# WiFiRadio.net
KiCad netlist of a schematic drawn in EAGLE
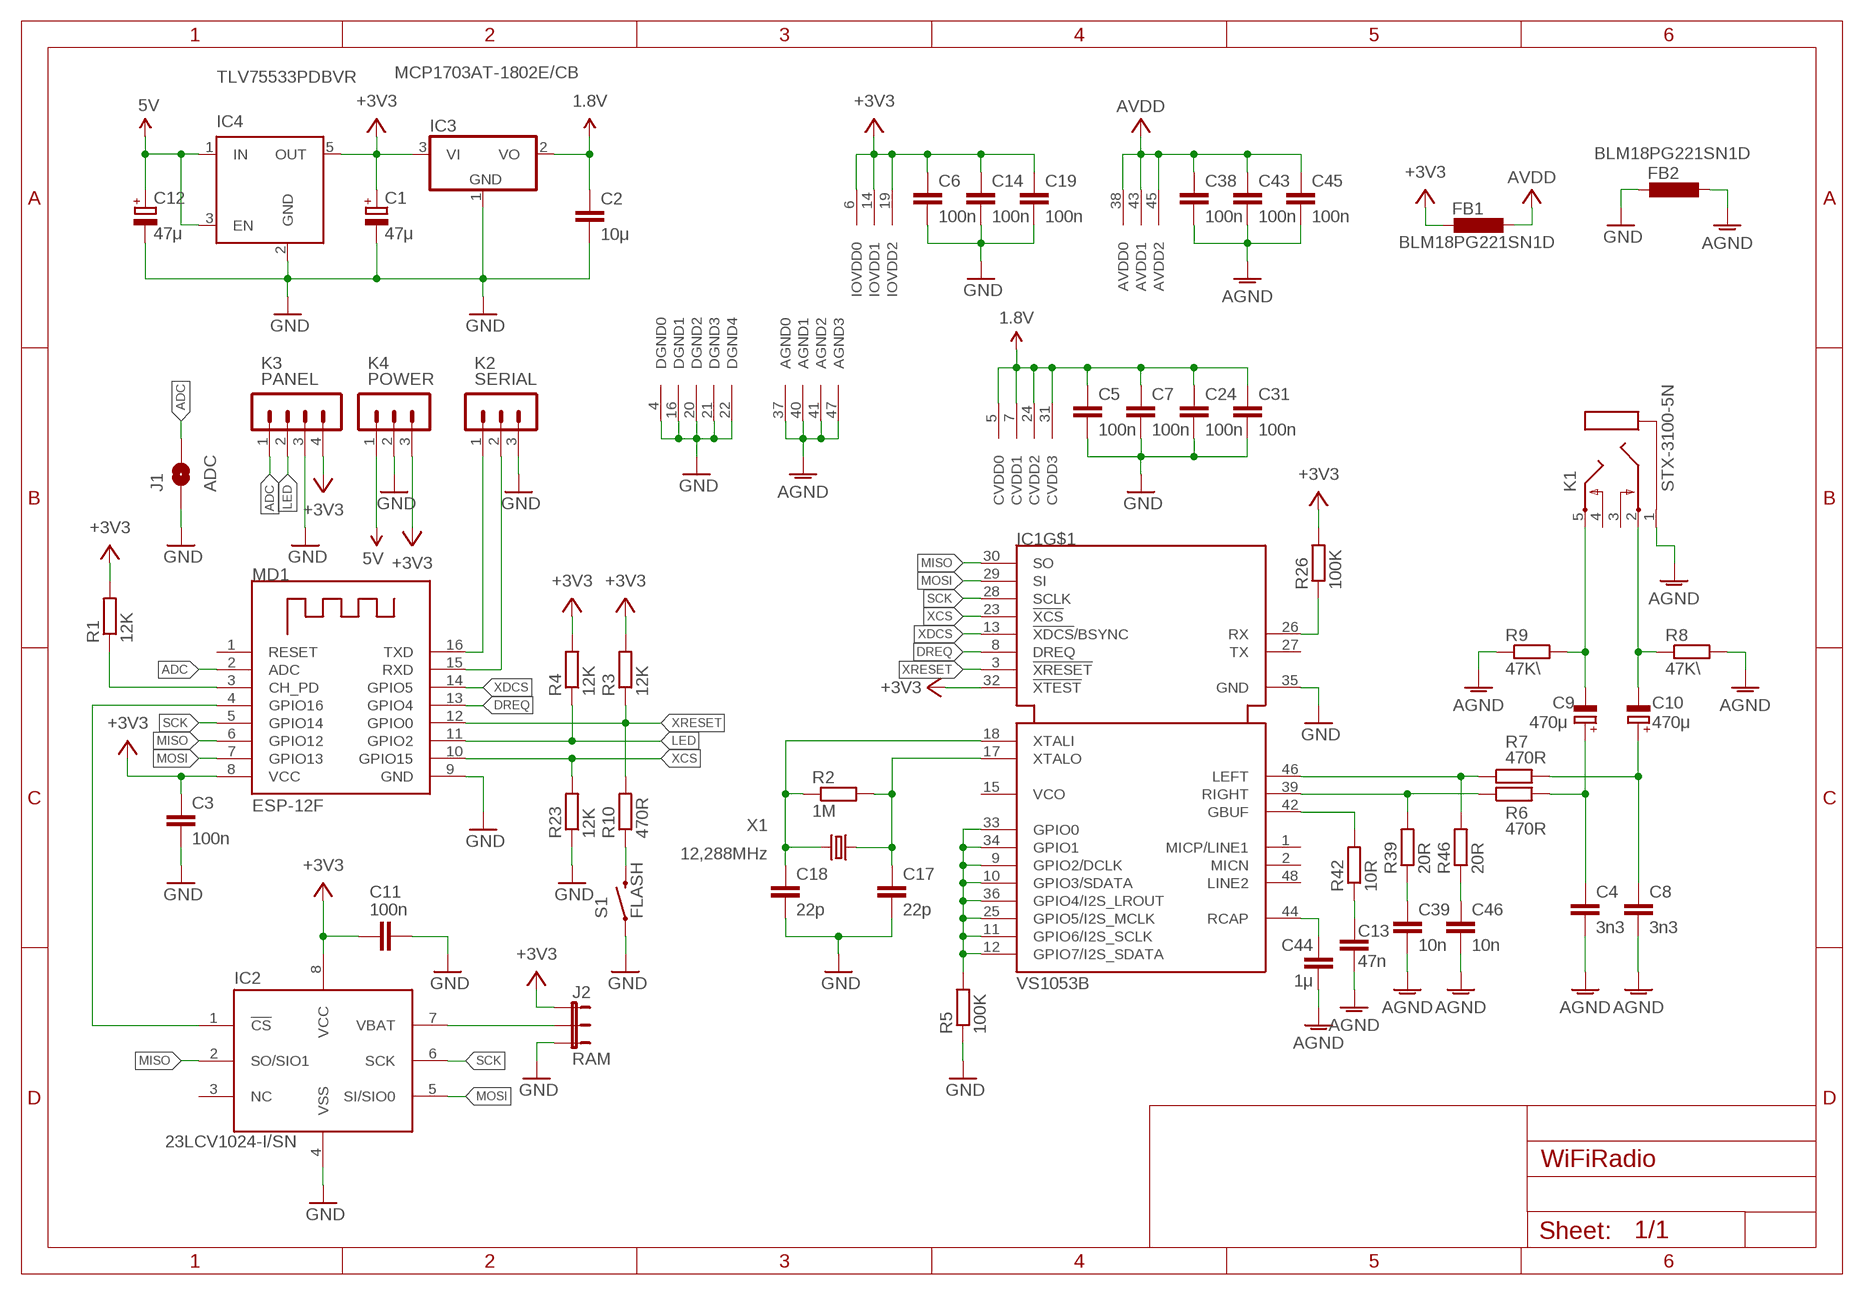
[diagram p0: schematic, sheet 1]

(export (version "E")
  (design (tool "Eeschema 10.0.6"))
  (components
    (comp (ref "C1")
      (value "47μ")
      (footprint "eagle-import:SMC_B")
      (libsource (lib "eagle-import") (part "rcl_334_CPOL-EUSMCB"))
    )
    (comp (ref "C2")
      (value "10μ")
      (footprint "eagle-import:C0805")
      (libsource (lib "eagle-import") (part "C-EUC0805"))
    )
    (comp (ref "C3")
      (value "100n")
      (footprint "eagle-import:C0603")
      (libsource (lib "eagle-import") (part "C-EUC0603"))
    )
    (comp (ref "C4")
      (value "3n3")
      (footprint "eagle-import:C0805")
      (libsource (lib "eagle-import") (part "C-EUC0805"))
    )
    (comp (ref "C5")
      (value "100n")
      (footprint "eagle-import:C0603")
      (libsource (lib "eagle-import") (part "C-EUC0603"))
    )
    (comp (ref "C6")
      (value "100n")
      (footprint "eagle-import:C0603")
      (libsource (lib "eagle-import") (part "C-EUC0603"))
    )
    (comp (ref "C7")
      (value "100n")
      (footprint "eagle-import:C0603")
      (libsource (lib "eagle-import") (part "C-EUC0603"))
    )
    (comp (ref "C8")
      (value "3n3")
      (footprint "eagle-import:C0805")
      (libsource (lib "eagle-import") (part "C-EUC0805"))
    )
    (comp (ref "C9")
      (value "470μ")
      (footprint "eagle-import:E3,5-8")
      (libsource (lib "eagle-import") (part "CPOL-EUE3.5-8"))
    )
    (comp (ref "C10")
      (value "470μ")
      (footprint "eagle-import:E3,5-8")
      (libsource (lib "eagle-import") (part "CPOL-EUE3.5-8"))
    )
    (comp (ref "C11")
      (value "100n")
      (footprint "eagle-import:C0603")
      (libsource (lib "eagle-import") (part "C-EUC0603"))
    )
    (comp (ref "C12")
      (value "47μ")
      (footprint "eagle-import:SMC_B")
      (libsource (lib "eagle-import") (part "rcl_334_CPOL-EUSMCB"))
    )
    (comp (ref "C13")
      (value "47n")
      (footprint "eagle-import:C0805")
      (libsource (lib "eagle-import") (part "C-EUC0805"))
    )
    (comp (ref "C14")
      (value "100n")
      (footprint "eagle-import:C0603")
      (libsource (lib "eagle-import") (part "C-EUC0603"))
    )
    (comp (ref "C17")
      (value "22p")
      (footprint "eagle-import:C0805")
      (libsource (lib "eagle-import") (part "C-EUC0805"))
    )
    (comp (ref "C18")
      (value "22p")
      (footprint "eagle-import:C0805")
      (libsource (lib "eagle-import") (part "C-EUC0805"))
    )
    (comp (ref "C19")
      (value "100n")
      (footprint "eagle-import:C0603")
      (libsource (lib "eagle-import") (part "C-EUC0603"))
    )
    (comp (ref "C24")
      (value "100n")
      (footprint "eagle-import:C0603")
      (libsource (lib "eagle-import") (part "C-EUC0603"))
    )
    (comp (ref "C31")
      (value "100n")
      (footprint "eagle-import:C0603")
      (libsource (lib "eagle-import") (part "C-EUC0603"))
    )
    (comp (ref "C38")
      (value "100n")
      (footprint "eagle-import:C0603")
      (libsource (lib "eagle-import") (part "C-EUC0603"))
    )
    (comp (ref "C39")
      (value "10n")
      (footprint "eagle-import:C0805")
      (libsource (lib "eagle-import") (part "C-EUC0805"))
    )
    (comp (ref "C43")
      (value "100n")
      (footprint "eagle-import:C0603")
      (libsource (lib "eagle-import") (part "C-EUC0603"))
    )
    (comp (ref "C44")
      (value "1μ")
      (footprint "eagle-import:C0805")
      (libsource (lib "eagle-import") (part "C-EUC0805"))
    )
    (comp (ref "C45")
      (value "100n")
      (footprint "eagle-import:C0603")
      (libsource (lib "eagle-import") (part "C-EUC0603"))
    )
    (comp (ref "C46")
      (value "10n")
      (footprint "eagle-import:C0805")
      (libsource (lib "eagle-import") (part "C-EUC0805"))
    )
    (comp (ref "FB1")
      (value "BLM18PG221SN1D")
      (footprint "eagle-import:L2012C")
      (libsource (lib "eagle-import") (part "L-EUL2012C"))
    )
    (comp (ref "FB2")
      (value "BLM18PG221SN1D")
      (footprint "eagle-import:L2012C")
      (libsource (lib "eagle-import") (part "L-EUL2012C"))
    )
    (comp (ref "IC1")
      (value "VS1053B")
      (footprint "eagle-import:LQFP48")
      (libsource (lib "eagle-import") (part "VS1053B"))
    )
    (comp (ref "IC2")
      (value "23LCV1024-I/SN")
      (footprint "eagle-import:SO-08")
      (libsource (lib "eagle-import") (part "23LCV1024-I/SN"))
    )
    (comp (ref "IC3")
      (value "MCP1703AT-1802E/CB")
      (footprint "eagle-import:SOT23")
      (libsource (lib "eagle-import") (part "MCP1703CB"))
    )
    (comp (ref "IC4")
      (value "TLV75533PDBVR")
      (footprint "eagle-import:SOT23-5")
      (libsource (lib "eagle-import") (part "TLV7555P-DBV"))
    )
    (comp (ref "J1")
      (value "ADC")
      (footprint "eagle-import:SJ_2S")
      (libsource (lib "eagle-import") (part "SOLDERJUMPER-OLDNC"))
    )
    (comp (ref "J2")
      (value "RAM")
      (footprint "eagle-import:SJ_3")
      (libsource (lib "eagle-import") (part "JUMPER-3SMD"))
    )
    (comp (ref "K1")
      (value "STX-3100-5N")
      (footprint "eagle-import:STX3100")
      (libsource (lib "eagle-import") (part "STEREOJACK"))
    )
    (comp (ref "K2")
      (value "SERIAL")
      (footprint "eagle-import:MA03-1")
      (libsource (lib "eagle-import") (part "MA03-1"))
    )
    (comp (ref "K3")
      (value "PANEL")
      (footprint "eagle-import:MA04-1")
      (libsource (lib "eagle-import") (part "MA04-1"))
    )
    (comp (ref "K4")
      (value "POWER")
      (footprint "eagle-import:MA03-1")
      (libsource (lib "eagle-import") (part "MA03-1"))
    )
    (comp (ref "MD1")
      (value "ESP-12F")
      (footprint "eagle-import:ESP-12F")
      (libsource (lib "eagle-import") (part "ESP-12F"))
    )
    (comp (ref "R1")
      (value "12K")
      (footprint "eagle-import:R0805")
      (libsource (lib "eagle-import") (part "R-EU_R0805"))
    )
    (comp (ref "R2")
      (value "1M")
      (footprint "eagle-import:R0805")
      (libsource (lib "eagle-import") (part "R-EU_R0805"))
    )
    (comp (ref "R3")
      (value "12K")
      (footprint "eagle-import:R0805")
      (libsource (lib "eagle-import") (part "R-EU_R0805"))
    )
    (comp (ref "R4")
      (value "12K")
      (footprint "eagle-import:R0805")
      (libsource (lib "eagle-import") (part "R-EU_R0805"))
    )
    (comp (ref "R5")
      (value "100K")
      (footprint "eagle-import:R0805")
      (libsource (lib "eagle-import") (part "R-EU_R0805"))
    )
    (comp (ref "R6")
      (value "470R")
      (footprint "eagle-import:R0805")
      (libsource (lib "eagle-import") (part "R-EU_R0805"))
    )
    (comp (ref "R7")
      (value "470R")
      (footprint "eagle-import:R0805")
      (libsource (lib "eagle-import") (part "R-EU_R0805"))
    )
    (comp (ref "R8")
      (value "47K\\")
      (footprint "eagle-import:R0805")
      (libsource (lib "eagle-import") (part "R-EU_R0805"))
    )
    (comp (ref "R9")
      (value "47K\\")
      (footprint "eagle-import:R0805")
      (libsource (lib "eagle-import") (part "R-EU_R0805"))
    )
    (comp (ref "R10")
      (value "470R")
      (footprint "eagle-import:R0805")
      (libsource (lib "eagle-import") (part "R-EU_R0805"))
    )
    (comp (ref "R23")
      (value "12K")
      (footprint "eagle-import:R0805")
      (libsource (lib "eagle-import") (part "R-EU_R0805"))
    )
    (comp (ref "R26")
      (value "100K")
      (footprint "eagle-import:R0805")
      (libsource (lib "eagle-import") (part "R-EU_R0805"))
    )
    (comp (ref "R39")
      (value "20R")
      (footprint "eagle-import:R0805")
      (libsource (lib "eagle-import") (part "R-EU_R0805"))
    )
    (comp (ref "R42")
      (value "10R")
      (footprint "eagle-import:R0805")
      (libsource (lib "eagle-import") (part "R-EU_R0805"))
    )
    (comp (ref "R46")
      (value "20R")
      (footprint "eagle-import:R0805")
      (libsource (lib "eagle-import") (part "R-EU_R0805"))
    )
    (comp (ref "S1")
      (value "FLASH")
      (footprint "eagle-import:TACTILE-SWITCH-SMD")
      (libsource (lib "eagle-import") (part "SWITCH-MOMENTARY-2SMD"))
    )
    (comp (ref "X1")
      (value "12,288MHz")
      (footprint "eagle-import:HC49_S")
      (libsource (lib "eagle-import") (part "CRYSTALHC49S"))
    )
  )
  (nets
    (net (code "1") (name "+3V3") (class "Default")
      (node (ref "C1") (pin "+") (pinfunction "+_+") (pintype "passive"))
      (node (ref "C11") (pin "1") (pinfunction "1_1") (pintype "passive"))
      (node (ref "C14") (pin "1") (pinfunction "1_1") (pintype "passive"))
      (node (ref "C19") (pin "1") (pinfunction "1_1") (pintype "passive"))
      (node (ref "C3") (pin "1") (pinfunction "1_1") (pintype "passive"))
      (node (ref "C6") (pin "1") (pinfunction "1_1") (pintype "passive"))
      (node (ref "FB1") (pin "2") (pinfunction "2_2") (pintype "passive"))
      (node (ref "IC1") (pin "14") (pinfunction "IOVDD1_14") (pintype "power_in"))
      (node (ref "IC1") (pin "19") (pinfunction "IOVDD2_19") (pintype "power_in"))
      (node (ref "IC1") (pin "32") (pinfunction "~{XTEST}_32") (pintype "input"))
      (node (ref "IC1") (pin "6") (pinfunction "IOVDD0_6") (pintype "power_in"))
      (node (ref "IC2") (pin "8") (pinfunction "VCC_8") (pintype "power_in"))
      (node (ref "IC3") (pin "3") (pinfunction "VI_3") (pintype "input"))
      (node (ref "IC4") (pin "5") (pinfunction "OUT_5") (pintype "output"))
      (node (ref "J2") (pin "1") (pinfunction "1_1") (pintype "passive"))
      (node (ref "K3") (pin "4") (pinfunction "4_4") (pintype "passive"))
      (node (ref "K4") (pin "3") (pinfunction "3_3") (pintype "passive"))
      (node (ref "MD1") (pin "8") (pinfunction "VCC_8") (pintype "power_in"))
      (node (ref "R1") (pin "2") (pinfunction "2_2") (pintype "passive"))
      (node (ref "R26") (pin "2") (pinfunction "2_2") (pintype "passive"))
      (node (ref "R3") (pin "2") (pinfunction "2_2") (pintype "passive"))
      (node (ref "R4") (pin "2") (pinfunction "2_2") (pintype "passive"))
    )
    (net (code "2") (name "1.8V") (class "Default")
      (node (ref "C2") (pin "1") (pinfunction "1_1") (pintype "passive"))
      (node (ref "C24") (pin "1") (pinfunction "1_1") (pintype "passive"))
      (node (ref "C31") (pin "1") (pinfunction "1_1") (pintype "passive"))
      (node (ref "C5") (pin "1") (pinfunction "1_1") (pintype "passive"))
      (node (ref "C7") (pin "1") (pinfunction "1_1") (pintype "passive"))
      (node (ref "IC1") (pin "24") (pinfunction "CVDD2_24") (pintype "power_in"))
      (node (ref "IC1") (pin "31") (pinfunction "CVDD3_31") (pintype "power_in"))
      (node (ref "IC1") (pin "5") (pinfunction "CVDD0_5") (pintype "power_in"))
      (node (ref "IC1") (pin "7") (pinfunction "CVDD1_7") (pintype "power_in"))
      (node (ref "IC3") (pin "2") (pinfunction "VO_2") (pintype "passive"))
    )
    (net (code "3") (name "5V") (class "Default")
      (node (ref "C12") (pin "+") (pinfunction "+_+") (pintype "passive"))
      (node (ref "IC4") (pin "1") (pinfunction "IN_1") (pintype "input"))
      (node (ref "IC4") (pin "3") (pinfunction "EN_3") (pintype "input"))
      (node (ref "K4") (pin "1") (pinfunction "1_1") (pintype "passive"))
    )
    (net (code "4") (name "ADC") (class "Default")
      (node (ref "J1") (pin "2") (pinfunction "2_2") (pintype "passive"))
      (node (ref "K3") (pin "1") (pinfunction "1_1") (pintype "passive"))
      (node (ref "MD1") (pin "2") (pinfunction "ADC_2") (pintype "passive"))
    )
    (net (code "5") (name "AGND") (class "Default")
      (node (ref "C13") (pin "2") (pinfunction "2_2") (pintype "passive"))
      (node (ref "C38") (pin "2") (pinfunction "2_2") (pintype "passive"))
      (node (ref "C39") (pin "2") (pinfunction "2_2") (pintype "passive"))
      (node (ref "C4") (pin "2") (pinfunction "2_2") (pintype "passive"))
      (node (ref "C43") (pin "2") (pinfunction "2_2") (pintype "passive"))
      (node (ref "C44") (pin "2") (pinfunction "2_2") (pintype "passive"))
      (node (ref "C45") (pin "2") (pinfunction "2_2") (pintype "passive"))
      (node (ref "C46") (pin "2") (pinfunction "2_2") (pintype "passive"))
      (node (ref "C8") (pin "2") (pinfunction "2_2") (pintype "passive"))
      (node (ref "FB2") (pin "1") (pinfunction "1_1") (pintype "passive"))
      (node (ref "IC1") (pin "37") (pinfunction "AGND0_37") (pintype "power_in"))
      (node (ref "IC1") (pin "40") (pinfunction "AGND1_40") (pintype "power_in"))
      (node (ref "IC1") (pin "41") (pinfunction "AGND2_41") (pintype "power_in"))
      (node (ref "IC1") (pin "47") (pinfunction "AGND3_47") (pintype "power_in"))
      (node (ref "K1") (pin "1") (pinfunction "1_1") (pintype "passive"))
      (node (ref "R8") (pin "2") (pinfunction "2_2") (pintype "passive"))
      (node (ref "R9") (pin "1") (pinfunction "1_1") (pintype "passive"))
    )
    (net (code "6") (name "AVDD") (class "Default")
      (node (ref "C38") (pin "1") (pinfunction "1_1") (pintype "passive"))
      (node (ref "C43") (pin "1") (pinfunction "1_1") (pintype "passive"))
      (node (ref "C45") (pin "1") (pinfunction "1_1") (pintype "passive"))
      (node (ref "FB1") (pin "1") (pinfunction "1_1") (pintype "passive"))
      (node (ref "IC1") (pin "38") (pinfunction "AVDD0_38") (pintype "power_in"))
      (node (ref "IC1") (pin "43") (pinfunction "AVDD1_43") (pintype "power_in"))
      (node (ref "IC1") (pin "45") (pinfunction "AVDD2_45") (pintype "power_in"))
    )
    (net (code "7") (name "DREQ") (class "Default")
      (node (ref "IC1") (pin "8") (pinfunction "DREQ_8") (pintype "output"))
      (node (ref "MD1") (pin "13") (pinfunction "GPIO4_13") (pintype "bidirectional"))
    )
    (net (code "8") (name "GND") (class "Default")
      (node (ref "C1") (pin "-") (pinfunction "-_-") (pintype "passive"))
      (node (ref "C11") (pin "2") (pinfunction "2_2") (pintype "passive"))
      (node (ref "C12") (pin "-") (pinfunction "-_-") (pintype "passive"))
      (node (ref "C14") (pin "2") (pinfunction "2_2") (pintype "passive"))
      (node (ref "C17") (pin "2") (pinfunction "2_2") (pintype "passive"))
      (node (ref "C18") (pin "2") (pinfunction "2_2") (pintype "passive"))
      (node (ref "C19") (pin "2") (pinfunction "2_2") (pintype "passive"))
      (node (ref "C2") (pin "2") (pinfunction "2_2") (pintype "passive"))
      (node (ref "C24") (pin "2") (pinfunction "2_2") (pintype "passive"))
      (node (ref "C3") (pin "2") (pinfunction "2_2") (pintype "passive"))
      (node (ref "C31") (pin "2") (pinfunction "2_2") (pintype "passive"))
      (node (ref "C5") (pin "2") (pinfunction "2_2") (pintype "passive"))
      (node (ref "C6") (pin "2") (pinfunction "2_2") (pintype "passive"))
      (node (ref "C7") (pin "2") (pinfunction "2_2") (pintype "passive"))
      (node (ref "FB2") (pin "2") (pinfunction "2_2") (pintype "passive"))
      (node (ref "IC1") (pin "16") (pinfunction "DGND1_16") (pintype "power_in"))
      (node (ref "IC1") (pin "20") (pinfunction "DGND2_20") (pintype "power_in"))
      (node (ref "IC1") (pin "21") (pinfunction "DGND3_21") (pintype "power_in"))
      (node (ref "IC1") (pin "22") (pinfunction "DGND4_22") (pintype "power_in"))
      (node (ref "IC1") (pin "35") (pinfunction "GND_35") (pintype "power_in"))
      (node (ref "IC1") (pin "4") (pinfunction "DGND0_4") (pintype "power_in"))
      (node (ref "IC2") (pin "4") (pinfunction "VSS_4") (pintype "power_in"))
      (node (ref "IC3") (pin "1") (pinfunction "GND_1") (pintype "passive"))
      (node (ref "IC4") (pin "2") (pinfunction "GND_2") (pintype "power_in"))
      (node (ref "J1") (pin "1") (pinfunction "1_1") (pintype "passive"))
      (node (ref "J2") (pin "3") (pinfunction "3_3") (pintype "passive"))
      (node (ref "K2") (pin "3") (pinfunction "3_3") (pintype "passive"))
      (node (ref "K3") (pin "3") (pinfunction "3_3") (pintype "passive"))
      (node (ref "K4") (pin "2") (pinfunction "2_2") (pintype "passive"))
      (node (ref "MD1") (pin "9") (pinfunction "GND_9") (pintype "power_in"))
      (node (ref "R23") (pin "1") (pinfunction "1_1") (pintype "passive"))
      (node (ref "R5") (pin "1") (pinfunction "1_1") (pintype "passive"))
      (node (ref "S1") (pin "1") (pinfunction "1_1") (pintype "passive"))
    )
    (net (code "9") (name "LED") (class "Default")
      (node (ref "K3") (pin "2") (pinfunction "2_2") (pintype "passive"))
      (node (ref "MD1") (pin "11") (pinfunction "GPIO2_11") (pintype "bidirectional"))
      (node (ref "R4") (pin "1") (pinfunction "1_1") (pintype "passive"))
    )
    (net (code "10") (name "MISO") (class "Default")
      (node (ref "IC1") (pin "30") (pinfunction "SO_30") (pintype "output"))
      (node (ref "IC2") (pin "2") (pinfunction "SO/SIO1_2") (pintype "bidirectional"))
      (node (ref "MD1") (pin "6") (pinfunction "GPIO12_6") (pintype "bidirectional"))
    )
    (net (code "11") (name "MOSI") (class "Default")
      (node (ref "IC1") (pin "29") (pinfunction "SI_29") (pintype "input"))
      (node (ref "IC2") (pin "5") (pinfunction "SI/SIO0_5") (pintype "bidirectional"))
      (node (ref "MD1") (pin "7") (pinfunction "GPIO13_7") (pintype "bidirectional"))
    )
    (net (code "12") (name "Net-(C4-Pad1)") (class "Default")
      (node (ref "C4") (pin "1") (pinfunction "1_1") (pintype "passive"))
      (node (ref "C9") (pin "+") (pinfunction "+_+") (pintype "passive"))
      (node (ref "R6") (pin "2") (pinfunction "2_2") (pintype "passive"))
    )
    (net (code "13") (name "Net-(C9-Pad-)") (class "Default")
      (node (ref "C9") (pin "-") (pinfunction "-_-") (pintype "passive"))
      (node (ref "K1") (pin "5") (pinfunction "5_5") (pintype "passive"))
      (node (ref "R9") (pin "2") (pinfunction "2_2") (pintype "passive"))
    )
    (net (code "14") (name "Net-(C10-Pad+)") (class "Default")
      (node (ref "C10") (pin "+") (pinfunction "+_+") (pintype "passive"))
      (node (ref "C8") (pin "1") (pinfunction "1_1") (pintype "passive"))
      (node (ref "R7") (pin "2") (pinfunction "2_2") (pintype "passive"))
    )
    (net (code "15") (name "Net-(C10-Pad-)") (class "Default")
      (node (ref "C10") (pin "-") (pinfunction "-_-") (pintype "passive"))
      (node (ref "K1") (pin "2") (pinfunction "2_2") (pintype "passive"))
      (node (ref "R8") (pin "1") (pinfunction "1_1") (pintype "passive"))
    )
    (net (code "16") (name "Net-(C13-Pad1)") (class "Default")
      (node (ref "C13") (pin "1") (pinfunction "1_1") (pintype "passive"))
      (node (ref "R42") (pin "1") (pinfunction "1_1") (pintype "passive"))
    )
    (net (code "17") (name "Net-(C39-Pad1)") (class "Default")
      (node (ref "C39") (pin "1") (pinfunction "1_1") (pintype "passive"))
      (node (ref "R39") (pin "1") (pinfunction "1_1") (pintype "passive"))
    )
    (net (code "18") (name "Net-(C46-Pad1)") (class "Default")
      (node (ref "C46") (pin "1") (pinfunction "1_1") (pintype "passive"))
      (node (ref "R46") (pin "1") (pinfunction "1_1") (pintype "passive"))
    )
    (net (code "19") (name "Net-(IC1A-GBUF)") (class "Default")
      (node (ref "IC1") (pin "42") (pinfunction "GBUF_42") (pintype "output"))
      (node (ref "R42") (pin "2") (pinfunction "2_2") (pintype "passive"))
    )
    (net (code "20") (name "Net-(IC1A-GPIO0)") (class "Default")
      (node (ref "IC1") (pin "10") (pinfunction "GPIO3/SDATA_10") (pintype "bidirectional"))
      (node (ref "IC1") (pin "11") (pinfunction "GPIO6/I2S_SCLK_11") (pintype "bidirectional"))
      (node (ref "IC1") (pin "12") (pinfunction "GPIO7/I2S_SDATA_12") (pintype "bidirectional"))
      (node (ref "IC1") (pin "25") (pinfunction "GPIO5/I2S_MCLK_25") (pintype "bidirectional"))
      (node (ref "IC1") (pin "33") (pinfunction "GPIO0_33") (pintype "bidirectional"))
      (node (ref "IC1") (pin "34") (pinfunction "GPIO1_34") (pintype "bidirectional"))
      (node (ref "IC1") (pin "36") (pinfunction "GPIO4/I2S_LROUT_36") (pintype "bidirectional"))
      (node (ref "IC1") (pin "9") (pinfunction "GPIO2/DCLK_9") (pintype "bidirectional"))
      (node (ref "R5") (pin "2") (pinfunction "2_2") (pintype "passive"))
    )
    (net (code "21") (name "Net-(IC1A-LEFT)") (class "Default")
      (node (ref "IC1") (pin "46") (pinfunction "LEFT_46") (pintype "output"))
      (node (ref "R46") (pin "2") (pinfunction "2_2") (pintype "passive"))
      (node (ref "R7") (pin "1") (pinfunction "1_1") (pintype "passive"))
    )
    (net (code "22") (name "Net-(IC1A-RCAP)") (class "Default")
      (node (ref "C44") (pin "1") (pinfunction "1_1") (pintype "passive"))
      (node (ref "IC1") (pin "44") (pinfunction "RCAP_44") (pintype "bidirectional"))
    )
    (net (code "23") (name "Net-(IC1A-RIGHT)") (class "Default")
      (node (ref "IC1") (pin "39") (pinfunction "RIGHT_39") (pintype "output"))
      (node (ref "R39") (pin "2") (pinfunction "2_2") (pintype "passive"))
      (node (ref "R6") (pin "1") (pinfunction "1_1") (pintype "passive"))
    )
    (net (code "24") (name "Net-(IC1A-RX)") (class "Default")
      (node (ref "IC1") (pin "26") (pinfunction "RX_26") (pintype "input"))
      (node (ref "R26") (pin "1") (pinfunction "1_1") (pintype "passive"))
    )
    (net (code "25") (name "Net-(IC1A-XTALI)") (class "Default")
      (node (ref "C18") (pin "1") (pinfunction "1_1") (pintype "passive"))
      (node (ref "IC1") (pin "18") (pinfunction "XTALI_18") (pintype "input"))
      (node (ref "R2") (pin "1") (pinfunction "1_1") (pintype "passive"))
      (node (ref "X1") (pin "2") (pinfunction "2_2") (pintype "passive"))
    )
    (net (code "26") (name "Net-(IC1A-XTALO)") (class "Default")
      (node (ref "C17") (pin "1") (pinfunction "1_1") (pintype "passive"))
      (node (ref "IC1") (pin "17") (pinfunction "XTALO_17") (pintype "output"))
      (node (ref "R2") (pin "2") (pinfunction "2_2") (pintype "passive"))
      (node (ref "X1") (pin "1") (pinfunction "1_1") (pintype "passive"))
    )
    (net (code "27") (name "Net-(IC2-VBAT)") (class "Default")
      (node (ref "IC2") (pin "7") (pinfunction "VBAT_7") (pintype "power_in"))
      (node (ref "J2") (pin "2") (pinfunction "2_2") (pintype "passive"))
    )
    (net (code "28") (name "Net-(IC2-~{CS})") (class "Default")
      (node (ref "IC2") (pin "1") (pinfunction "~{CS}_1") (pintype "input"))
      (node (ref "MD1") (pin "4") (pinfunction "GPIO16_4") (pintype "bidirectional"))
    )
    (net (code "29") (name "Net-(MD1-CH_PD)") (class "Default")
      (node (ref "MD1") (pin "3") (pinfunction "CH_PD_3") (pintype "input"))
      (node (ref "R1") (pin "1") (pinfunction "1_1") (pintype "passive"))
    )
    (net (code "30") (name "Net-(MD1-RXD)") (class "Default")
      (node (ref "K2") (pin "2") (pinfunction "2_2") (pintype "passive"))
      (node (ref "MD1") (pin "15") (pinfunction "RXD_15") (pintype "input"))
    )
    (net (code "31") (name "Net-(MD1-TXD)") (class "Default")
      (node (ref "K2") (pin "1") (pinfunction "1_1") (pintype "passive"))
      (node (ref "MD1") (pin "16") (pinfunction "TXD_16") (pintype "output"))
    )
    (net (code "32") (name "Net-(S1-2)") (class "Default")
      (node (ref "R10") (pin "1") (pinfunction "1_1") (pintype "passive"))
      (node (ref "S1") (pin "3") (pinfunction "2_3") (pintype "passive"))
    )
    (net (code "33") (name "SCK") (class "Default")
      (node (ref "IC1") (pin "28") (pinfunction "SCLK_28") (pintype "input"))
      (node (ref "IC2") (pin "6") (pinfunction "SCK_6") (pintype "input"))
      (node (ref "MD1") (pin "5") (pinfunction "GPIO14_5") (pintype "bidirectional"))
    )
    (net (code "34") (name "XCS") (class "Default")
      (node (ref "IC1") (pin "23") (pinfunction "~{XCS}_23") (pintype "input"))
      (node (ref "MD1") (pin "10") (pinfunction "GPIO15_10") (pintype "bidirectional"))
      (node (ref "R23") (pin "2") (pinfunction "2_2") (pintype "passive"))
    )
    (net (code "35") (name "XDCS") (class "Default")
      (node (ref "IC1") (pin "13") (pinfunction "~{XDCS}/BSYNC_13") (pintype "input"))
      (node (ref "MD1") (pin "14") (pinfunction "GPIO5_14") (pintype "bidirectional"))
    )
    (net (code "36") (name "XRESET") (class "Default")
      (node (ref "IC1") (pin "3") (pinfunction "~{XRESET}_3") (pintype "input"))
      (node (ref "MD1") (pin "12") (pinfunction "GPIO0_12") (pintype "bidirectional"))
      (node (ref "R10") (pin "2") (pinfunction "2_2") (pintype "passive"))
      (node (ref "R3") (pin "1") (pinfunction "1_1") (pintype "passive"))
    )
    (net (code "37") (name "unconnected-(IC1A-LINE2-Pad48)") (class "Default")
      (node (ref "IC1") (pin "48") (pinfunction "LINE2_48") (pintype "input"))
    )
    (net (code "38") (name "unconnected-(IC1A-MICN-Pad2)") (class "Default")
      (node (ref "IC1") (pin "2") (pinfunction "MICN_2") (pintype "input"))
    )
    (net (code "39") (name "unconnected-(IC1A-MICP{slash}LINE1-Pad1)") (class "Default")
      (node (ref "IC1") (pin "1") (pinfunction "MICP/LINE1_1") (pintype "input"))
    )
    (net (code "40") (name "unconnected-(IC1A-TX-Pad27)") (class "Default")
      (node (ref "IC1") (pin "27") (pinfunction "TX_27") (pintype "output"))
    )
    (net (code "41") (name "unconnected-(IC1A-VCO-Pad15)") (class "Default")
      (node (ref "IC1") (pin "15") (pinfunction "VCO_15") (pintype "output"))
    )
    (net (code "42") (name "unconnected-(IC2-NC-Pad3)") (class "Default")
      (node (ref "IC2") (pin "3") (pinfunction "NC_3") (pintype "no_connect"))
    )
    (net (code "43") (name "unconnected-(K1-Pad3)") (class "Default")
      (node (ref "K1") (pin "3") (pinfunction "3_3") (pintype "passive"))
    )
    (net (code "44") (name "unconnected-(K1-Pad4)") (class "Default")
      (node (ref "K1") (pin "4") (pinfunction "4_4") (pintype "passive"))
    )
    (net (code "45") (name "unconnected-(MD1-RESET-Pad1)") (class "Default")
      (node (ref "MD1") (pin "1") (pinfunction "RESET_1") (pintype "input"))
    )
  )
)
